# NEO_Board_V2.net
KiCad netlist of a schematic drawn in EAGLE
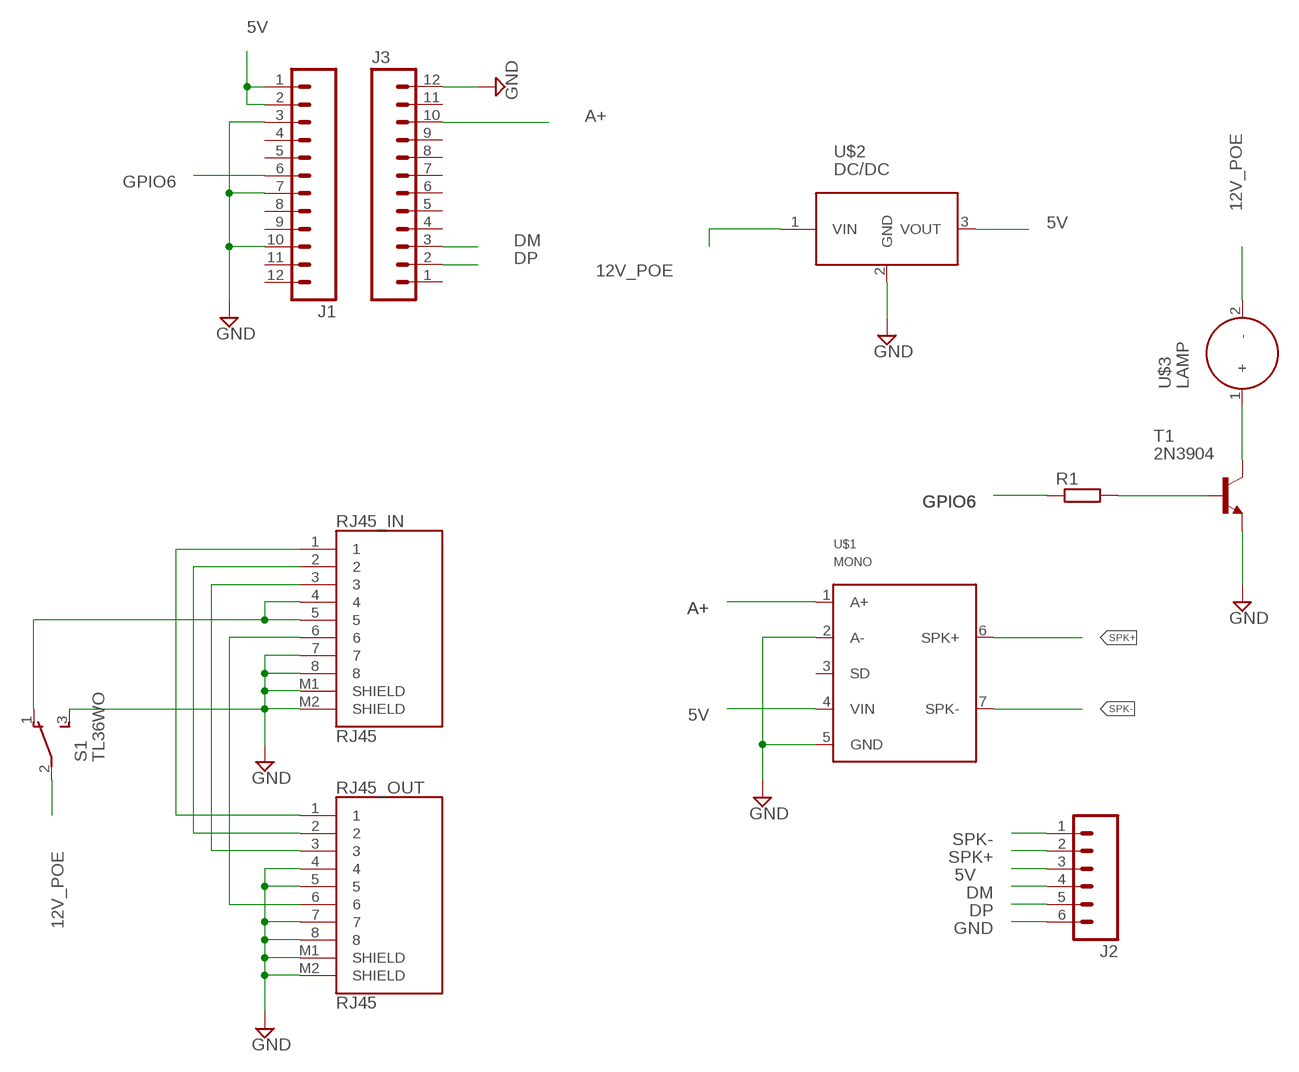
[diagram p0: schematic, sheet 1]

(export (version "E")
  (design (tool "Eeschema 10.0.6"))
  (components
    (comp (ref "J1")
      (value "M12PTH")
      (footprint "eagle-import:1X12")
      (libsource (lib "eagle-import") (part "M12PTH"))
    )
    (comp (ref "J2")
      (value "M06NO_SILK_FEMALE_PTH")
      (footprint "eagle-import:1X06_NO_SILK")
      (libsource (lib "eagle-import") (part "M06NO_SILK_FEMALE_PTH"))
    )
    (comp (ref "J3")
      (value "M12PTH")
      (footprint "eagle-import:1X12")
      (libsource (lib "eagle-import") (part "M12PTH"))
    )
    (comp (ref "R1")
      (value "R-EU_0207/10")
      (footprint "eagle-import:0207_10")
      (libsource (lib "eagle-import") (part "R-EU_0207/10"))
    )
    (comp (ref "RJ45_IN")
      (value "RJ45")
      (footprint "eagle-import:RJ45")
      (libsource (lib "eagle-import") (part "RJ45"))
    )
    (comp (ref "RJ45_OUT")
      (value "RJ45")
      (footprint "eagle-import:RJ45")
      (libsource (lib "eagle-import") (part "RJ45"))
    )
    (comp (ref "S1")
      (value "TL36WO")
      (footprint "eagle-import:TL3XWO")
      (libsource (lib "eagle-import") (part "TL36WO"))
    )
    (comp (ref "T1")
      (value "2N3904")
      (footprint "eagle-import:TO92")
      (libsource (lib "eagle-import") (part "2N3904"))
    )
    (comp (ref "U$1")
      (value "MONO")
      (footprint "eagle-import:MONO_AMP")
      (libsource (lib "eagle-import") (part "MONO"))
    )
    (comp (ref "U$2")
      (value "DC/DC")
      (footprint "eagle-import:DC_DC")
      (libsource (lib "eagle-import") (part "DC/DC"))
    )
    (comp (ref "U$3")
      (value "LAMP")
      (footprint "eagle-import:LAMP")
      (libsource (lib "eagle-import") (part "LAMP"))
    )
  )
  (nets
    (net (code "1") (name "/5V") (class "Default")
      (node (ref "J1") (pin "1") (pinfunction "1_1") (pintype "passive"))
      (node (ref "J1") (pin "2") (pinfunction "2_2") (pintype "passive"))
      (node (ref "J2") (pin "3") (pinfunction "3_3") (pintype "passive"))
      (node (ref "U$1") (pin "4") (pinfunction "VIN_4") (pintype "bidirectional"))
      (node (ref "U$2") (pin "3") (pinfunction "VOUT_3") (pintype "bidirectional"))
    )
    (net (code "2") (name "/12V_POE") (class "Default")
      (node (ref "S1") (pin "2") (pinfunction "P_2") (pintype "passive"))
      (node (ref "U$2") (pin "1") (pinfunction "VIN_1") (pintype "bidirectional"))
      (node (ref "U$3") (pin "2") (pinfunction "-_2") (pintype "bidirectional"))
    )
    (net (code "3") (name "/A+") (class "Default")
      (node (ref "J3") (pin "10") (pinfunction "10_10") (pintype "passive"))
      (node (ref "U$1") (pin "1") (pinfunction "A+_1") (pintype "bidirectional"))
    )
    (net (code "4") (name "/DM") (class "Default")
      (node (ref "J2") (pin "4") (pinfunction "4_4") (pintype "passive"))
      (node (ref "J3") (pin "3") (pinfunction "3_3") (pintype "passive"))
    )
    (net (code "5") (name "/DP") (class "Default")
      (node (ref "J2") (pin "5") (pinfunction "5_5") (pintype "passive"))
      (node (ref "J3") (pin "2") (pinfunction "2_2") (pintype "passive"))
    )
    (net (code "6") (name "/GPIO6") (class "Default")
      (node (ref "J1") (pin "6") (pinfunction "6_6") (pintype "passive"))
      (node (ref "R1") (pin "1") (pinfunction "1_1") (pintype "passive"))
    )
    (net (code "7") (name "GND") (class "Default")
      (node (ref "J1") (pin "10") (pinfunction "10_10") (pintype "passive"))
      (node (ref "J1") (pin "3") (pinfunction "3_3") (pintype "passive"))
      (node (ref "J1") (pin "7") (pinfunction "7_7") (pintype "passive"))
      (node (ref "J2") (pin "6") (pinfunction "6_6") (pintype "passive"))
      (node (ref "J3") (pin "12") (pinfunction "12_12") (pintype "passive"))
      (node (ref "RJ45_IN") (pin "7") (pinfunction "7_7") (pintype "bidirectional"))
      (node (ref "RJ45_IN") (pin "8") (pinfunction "8_8") (pintype "bidirectional"))
      (node (ref "RJ45_IN") (pin "M1") (pinfunction "SHIELD_M1") (pintype "bidirectional"))
      (node (ref "RJ45_IN") (pin "M2") (pinfunction "SHIELD_M2") (pintype "bidirectional"))
      (node (ref "RJ45_OUT") (pin "4") (pinfunction "4_4") (pintype "bidirectional"))
      (node (ref "RJ45_OUT") (pin "5") (pinfunction "5_5") (pintype "bidirectional"))
      (node (ref "RJ45_OUT") (pin "7") (pinfunction "7_7") (pintype "bidirectional"))
      (node (ref "RJ45_OUT") (pin "8") (pinfunction "8_8") (pintype "bidirectional"))
      (node (ref "RJ45_OUT") (pin "M1") (pinfunction "SHIELD_M1") (pintype "bidirectional"))
      (node (ref "RJ45_OUT") (pin "M2") (pinfunction "SHIELD_M2") (pintype "bidirectional"))
      (node (ref "S1") (pin "3") (pinfunction "S_3") (pintype "passive"))
      (node (ref "T1") (pin "3") (pinfunction "E_3") (pintype "passive"))
      (node (ref "U$1") (pin "2") (pinfunction "A-_2") (pintype "bidirectional"))
      (node (ref "U$1") (pin "5") (pinfunction "GND_5") (pintype "bidirectional"))
      (node (ref "U$2") (pin "2") (pinfunction "GND_2") (pintype "bidirectional"))
    )
    (net (code "8") (name "Net-(RJ45_IN-Pad1)") (class "Default")
      (node (ref "RJ45_IN") (pin "1") (pinfunction "1_1") (pintype "bidirectional"))
      (node (ref "RJ45_OUT") (pin "1") (pinfunction "1_1") (pintype "bidirectional"))
    )
    (net (code "9") (name "Net-(RJ45_IN-Pad2)") (class "Default")
      (node (ref "RJ45_IN") (pin "2") (pinfunction "2_2") (pintype "bidirectional"))
      (node (ref "RJ45_OUT") (pin "2") (pinfunction "2_2") (pintype "bidirectional"))
    )
    (net (code "10") (name "Net-(RJ45_IN-Pad3)") (class "Default")
      (node (ref "RJ45_IN") (pin "3") (pinfunction "3_3") (pintype "bidirectional"))
      (node (ref "RJ45_OUT") (pin "3") (pinfunction "3_3") (pintype "bidirectional"))
    )
    (net (code "11") (name "Net-(RJ45_IN-Pad6)") (class "Default")
      (node (ref "RJ45_IN") (pin "6") (pinfunction "6_6") (pintype "bidirectional"))
      (node (ref "RJ45_OUT") (pin "6") (pinfunction "6_6") (pintype "bidirectional"))
    )
    (net (code "12") (name "Net-(S1-O)") (class "Default")
      (node (ref "RJ45_IN") (pin "4") (pinfunction "4_4") (pintype "bidirectional"))
      (node (ref "RJ45_IN") (pin "5") (pinfunction "5_5") (pintype "bidirectional"))
      (node (ref "S1") (pin "1") (pinfunction "O_1") (pintype "passive"))
    )
    (net (code "13") (name "Net-(T1-B)") (class "Default")
      (node (ref "R1") (pin "2") (pinfunction "2_2") (pintype "passive"))
      (node (ref "T1") (pin "2") (pinfunction "B_2") (pintype "passive"))
    )
    (net (code "14") (name "Net-(T1-C)") (class "Default")
      (node (ref "T1") (pin "1") (pinfunction "C_1") (pintype "passive"))
      (node (ref "U$3") (pin "1") (pinfunction "+_1") (pintype "bidirectional"))
    )
    (net (code "15") (name "SPK+") (class "Default")
      (node (ref "J2") (pin "2") (pinfunction "2_2") (pintype "passive"))
      (node (ref "U$1") (pin "6") (pinfunction "SPK+_6") (pintype "bidirectional"))
    )
    (net (code "16") (name "SPK-") (class "Default")
      (node (ref "J2") (pin "1") (pinfunction "1_1") (pintype "passive"))
      (node (ref "U$1") (pin "7") (pinfunction "SPK-_7") (pintype "bidirectional"))
    )
    (net (code "17") (name "unconnected-(J1-Pad4)") (class "Default")
      (node (ref "J1") (pin "4") (pinfunction "4_4") (pintype "passive"))
    )
    (net (code "18") (name "unconnected-(J1-Pad5)") (class "Default")
      (node (ref "J1") (pin "5") (pinfunction "5_5") (pintype "passive"))
    )
    (net (code "19") (name "unconnected-(J1-Pad8)") (class "Default")
      (node (ref "J1") (pin "8") (pinfunction "8_8") (pintype "passive"))
    )
    (net (code "20") (name "unconnected-(J1-Pad9)") (class "Default")
      (node (ref "J1") (pin "9") (pinfunction "9_9") (pintype "passive"))
    )
    (net (code "21") (name "unconnected-(J1-Pad11)") (class "Default")
      (node (ref "J1") (pin "11") (pinfunction "11_11") (pintype "passive"))
    )
    (net (code "22") (name "unconnected-(J1-Pad12)") (class "Default")
      (node (ref "J1") (pin "12") (pinfunction "12_12") (pintype "passive"))
    )
    (net (code "23") (name "unconnected-(J3-Pad1)") (class "Default")
      (node (ref "J3") (pin "1") (pinfunction "1_1") (pintype "passive"))
    )
    (net (code "24") (name "unconnected-(J3-Pad4)") (class "Default")
      (node (ref "J3") (pin "4") (pinfunction "4_4") (pintype "passive"))
    )
    (net (code "25") (name "unconnected-(J3-Pad5)") (class "Default")
      (node (ref "J3") (pin "5") (pinfunction "5_5") (pintype "passive"))
    )
    (net (code "26") (name "unconnected-(J3-Pad6)") (class "Default")
      (node (ref "J3") (pin "6") (pinfunction "6_6") (pintype "passive"))
    )
    (net (code "27") (name "unconnected-(J3-Pad7)") (class "Default")
      (node (ref "J3") (pin "7") (pinfunction "7_7") (pintype "passive"))
    )
    (net (code "28") (name "unconnected-(J3-Pad8)") (class "Default")
      (node (ref "J3") (pin "8") (pinfunction "8_8") (pintype "passive"))
    )
    (net (code "29") (name "unconnected-(J3-Pad9)") (class "Default")
      (node (ref "J3") (pin "9") (pinfunction "9_9") (pintype "passive"))
    )
    (net (code "30") (name "unconnected-(J3-Pad11)") (class "Default")
      (node (ref "J3") (pin "11") (pinfunction "11_11") (pintype "passive"))
    )
    (net (code "31") (name "unconnected-(U$1-SD-Pad3)") (class "Default")
      (node (ref "U$1") (pin "3") (pinfunction "SD_3") (pintype "bidirectional"))
    )
  )
)
